# MM_Performer.net
KiCad netlist of a schematic drawn in EAGLE
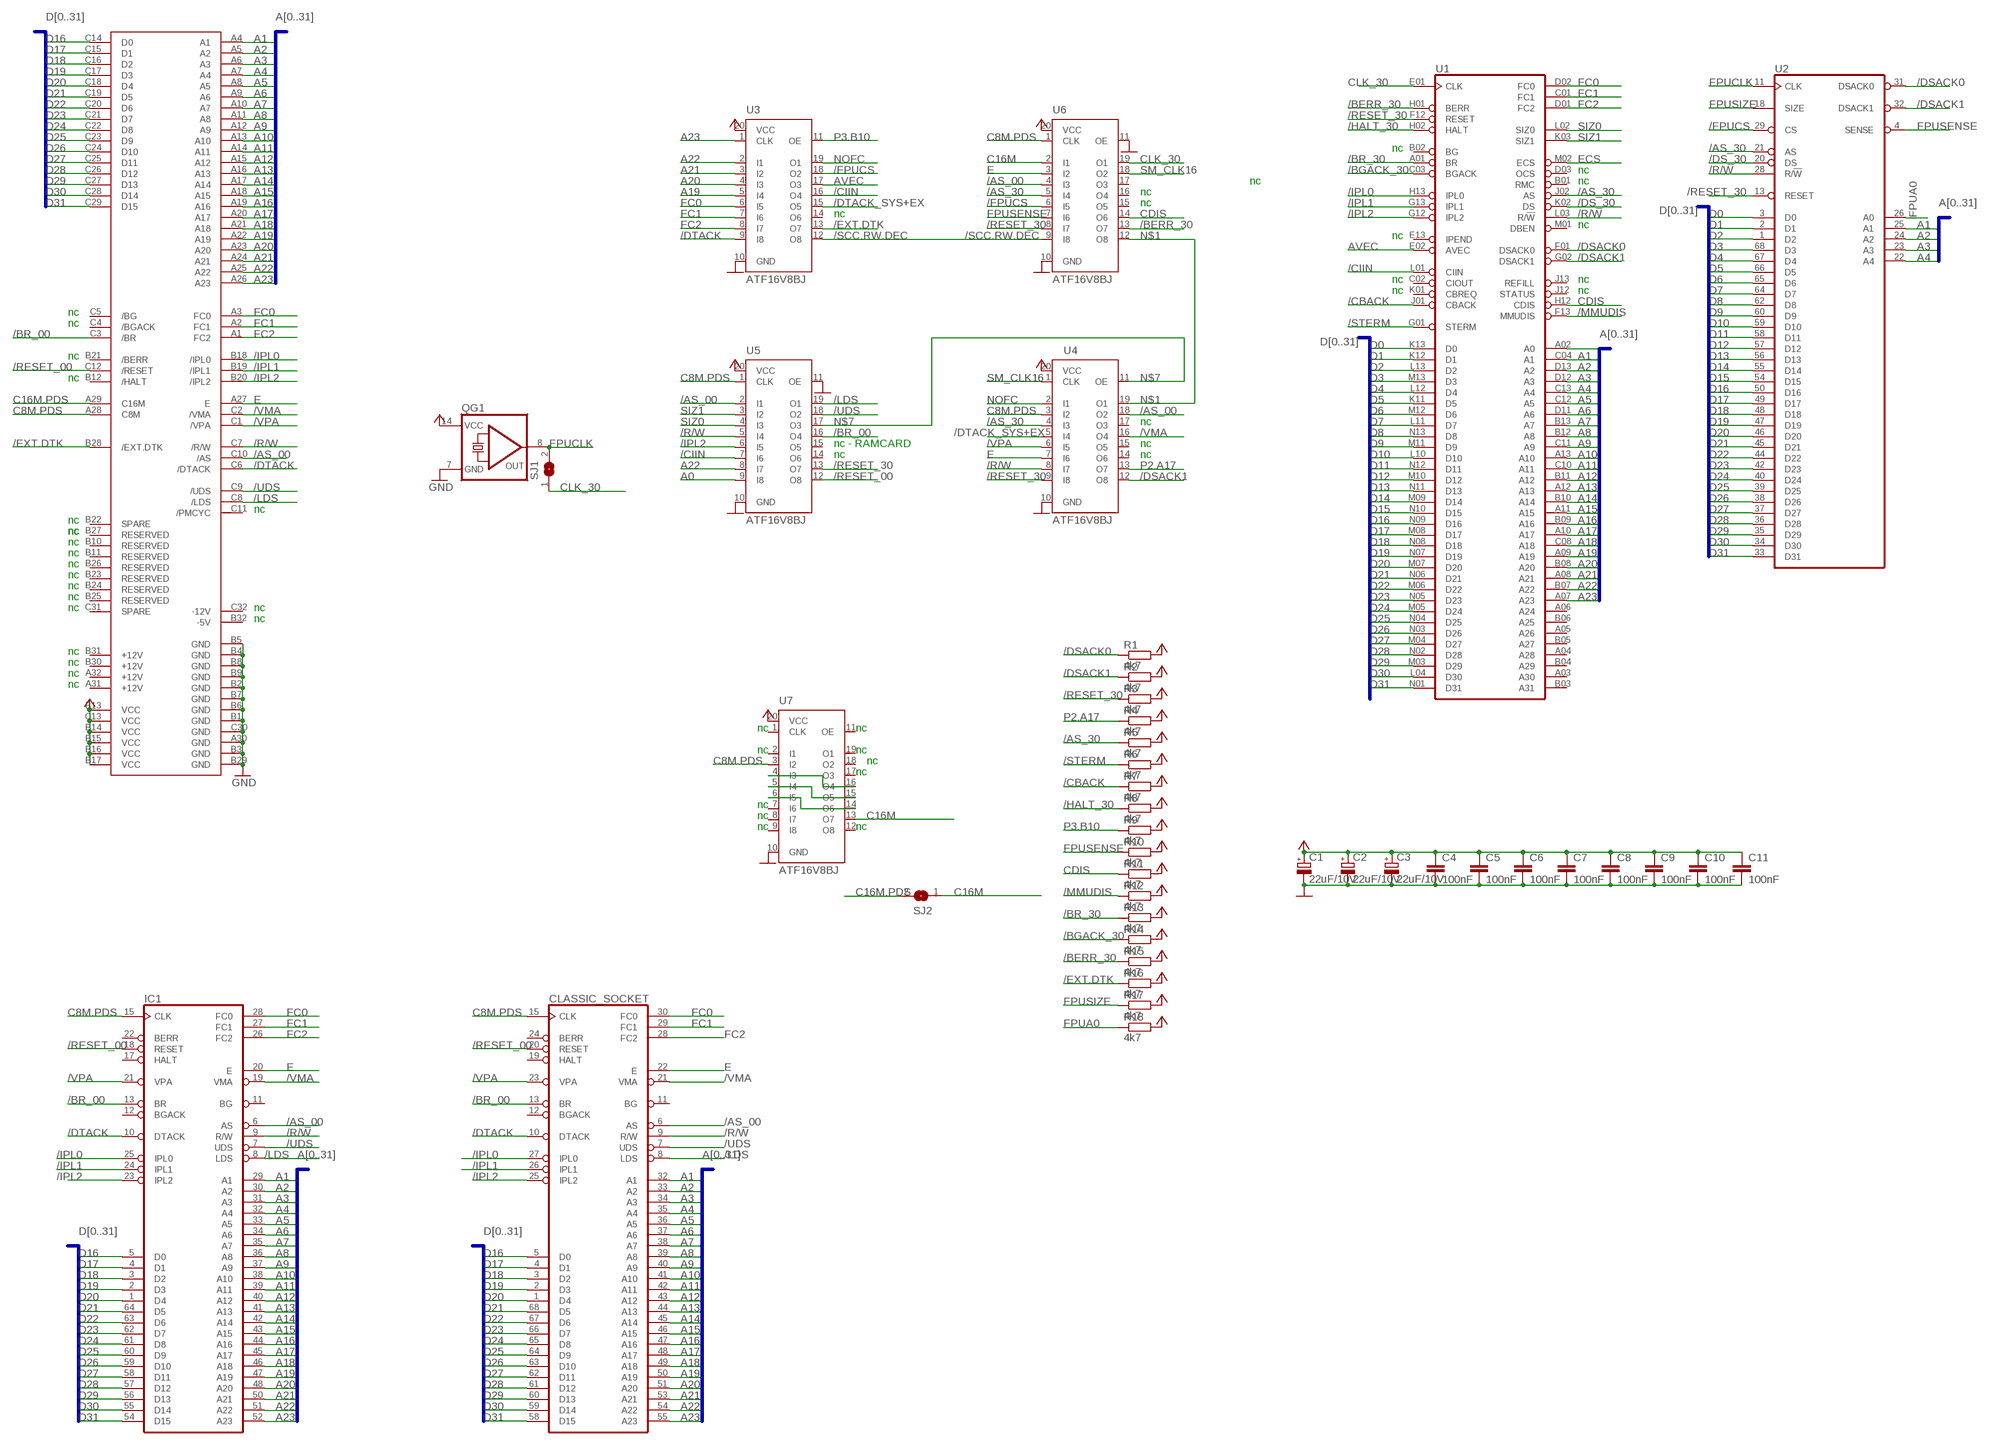
[diagram p0: schematic, sheet 1]

(export (version "E")
  (design (tool "Eeschema 10.0.6"))
  (components
    (comp (ref "C1")
      (value "22uF/10V")
      (footprint "eagle-import:C_6032-28W")
      (libsource (lib "eagle-import") (part "CPOL-EUC/6032-28W"))
    )
    (comp (ref "C2")
      (value "22uF/10V")
      (footprint "eagle-import:C_6032-28W")
      (libsource (lib "eagle-import") (part "CPOL-EUC/6032-28W"))
    )
    (comp (ref "C3")
      (value "22uF/10V")
      (footprint "eagle-import:C_6032-28W")
      (libsource (lib "eagle-import") (part "CPOL-EUC/6032-28W"))
    )
    (comp (ref "C4")
      (value "100nF")
      (footprint "eagle-import:C1206")
      (libsource (lib "eagle-import") (part "C-EUC1206"))
    )
    (comp (ref "C5")
      (value "100nF")
      (footprint "eagle-import:C1206")
      (libsource (lib "eagle-import") (part "C-EUC1206"))
    )
    (comp (ref "C6")
      (value "100nF")
      (footprint "eagle-import:C1206")
      (libsource (lib "eagle-import") (part "C-EUC1206"))
    )
    (comp (ref "C7")
      (value "100nF")
      (footprint "eagle-import:C1206")
      (libsource (lib "eagle-import") (part "C-EUC1206"))
    )
    (comp (ref "C8")
      (value "100nF")
      (footprint "eagle-import:C1206")
      (libsource (lib "eagle-import") (part "C-EUC1206"))
    )
    (comp (ref "C9")
      (value "100nF")
      (footprint "eagle-import:C1206")
      (libsource (lib "eagle-import") (part "C-EUC1206"))
    )
    (comp (ref "C10")
      (value "100nF")
      (footprint "eagle-import:C1206")
      (libsource (lib "eagle-import") (part "C-EUC1206"))
    )
    (comp (ref "C11")
      (value "100nF")
      (footprint "eagle-import:C1206")
      (libsource (lib "eagle-import") (part "C-EUC1206"))
    )
    (comp (ref "CLASSIC_SOCKET")
      (value "MC68000FN-SOC")
      (footprint "eagle-import:PLCC68-S")
      (libsource (lib "eagle-import") (part "MC68000FN-SOC"))
    )
    (comp (ref "IC1")
      (value "MC68000P")
      (footprint "eagle-import:DIL64")
      (libsource (lib "eagle-import") (part "MC68000P"))
    )
    (comp (ref "QG1")
      (value "QG5860")
      (footprint "eagle-import:DIL14S")
      (libsource (lib "eagle-import") (part "QG5860"))
    )
    (comp (ref "R1")
      (value "4k7")
      (footprint "eagle-import:R1206")
      (libsource (lib "eagle-import") (part "R-EU_R1206"))
    )
    (comp (ref "R2")
      (value "4k7")
      (footprint "eagle-import:R1206")
      (libsource (lib "eagle-import") (part "R-EU_R1206"))
    )
    (comp (ref "R3")
      (value "4k7")
      (footprint "eagle-import:R1206")
      (libsource (lib "eagle-import") (part "R-EU_R1206"))
    )
    (comp (ref "R4")
      (value "4k7")
      (footprint "eagle-import:R1206")
      (libsource (lib "eagle-import") (part "R-EU_R1206"))
    )
    (comp (ref "R5")
      (value "4k7")
      (footprint "eagle-import:R1206")
      (libsource (lib "eagle-import") (part "R-EU_R1206"))
    )
    (comp (ref "R6")
      (value "4k7")
      (footprint "eagle-import:R1206")
      (libsource (lib "eagle-import") (part "R-EU_R1206"))
    )
    (comp (ref "R7")
      (value "4k7")
      (footprint "eagle-import:R1206")
      (libsource (lib "eagle-import") (part "R-EU_R1206"))
    )
    (comp (ref "R8")
      (value "4k7")
      (footprint "eagle-import:R1206")
      (libsource (lib "eagle-import") (part "R-EU_R1206"))
    )
    (comp (ref "R9")
      (value "4k7")
      (footprint "eagle-import:R1206")
      (libsource (lib "eagle-import") (part "R-EU_R1206"))
    )
    (comp (ref "R10")
      (value "4k7")
      (footprint "eagle-import:R1206")
      (libsource (lib "eagle-import") (part "R-EU_R1206"))
    )
    (comp (ref "R11")
      (value "4k7")
      (footprint "eagle-import:R1206")
      (libsource (lib "eagle-import") (part "R-EU_R1206"))
    )
    (comp (ref "R12")
      (value "4k7")
      (footprint "eagle-import:R1206")
      (libsource (lib "eagle-import") (part "R-EU_R1206"))
    )
    (comp (ref "R13")
      (value "4k7")
      (footprint "eagle-import:R1206")
      (libsource (lib "eagle-import") (part "R-EU_R1206"))
    )
    (comp (ref "R14")
      (value "4k7")
      (footprint "eagle-import:R1206")
      (libsource (lib "eagle-import") (part "R-EU_R1206"))
    )
    (comp (ref "R15")
      (value "4k7")
      (footprint "eagle-import:R1206")
      (libsource (lib "eagle-import") (part "R-EU_R1206"))
    )
    (comp (ref "R16")
      (value "4k7")
      (footprint "eagle-import:R1206")
      (libsource (lib "eagle-import") (part "R-EU_R1206"))
    )
    (comp (ref "R17")
      (value "4k7")
      (footprint "eagle-import:R1206")
      (libsource (lib "eagle-import") (part "R-EU_R1206"))
    )
    (comp (ref "R18")
      (value "4k7")
      (footprint "eagle-import:R1206")
      (libsource (lib "eagle-import") (part "R-EU_R1206"))
    )
    (comp (ref "SJ1") (value "SJ") (footprint "eagle-import:SJ") (libsource (lib "eagle-import") (part "SJ")))
    (comp (ref "SJ2") (value "SJ") (footprint "eagle-import:SJ") (libsource (lib "eagle-import") (part "SJ")))
    (comp (ref "U$1")
      (value "MAC_SE_PDS")
      (footprint "eagle-import:MABC96_MIRROR")
      (libsource (lib "eagle-import") (part "MAC_SE_PDS"))
    )
    (comp (ref "U1")
      (value "MC68030RC")
      (footprint "eagle-import:MPGA128")
      (fields (field (name "MF") "MOTOROLA") (field (name "MPN") "MC68030RC50C"))
      (libsource (lib "eagle-import") (part "MC68030RC"))
    )
    (comp (ref "U2")
      (value "MC68881FN-SOC")
      (footprint "eagle-import:PLCC68-S")
      (libsource (lib "eagle-import") (part "MC68881FN-SOC"))
    )
    (comp (ref "U3")
      (value "ATF16V8BJ")
      (footprint "eagle-import:PLCC20")
      (fields (field (name "MPN") "ATF16V8CZ-15JU"))
      (libsource (lib "eagle-import") (part "ATF16V8BJ"))
    )
    (comp (ref "U4")
      (value "ATF16V8BJ")
      (footprint "eagle-import:PLCC20")
      (fields (field (name "MPN") "ATF16V8CZ-15JU"))
      (libsource (lib "eagle-import") (part "ATF16V8BJ"))
    )
    (comp (ref "U5")
      (value "ATF16V8BJ")
      (footprint "eagle-import:PLCC20")
      (fields (field (name "MPN") "ATF16V8CZ-15JU"))
      (libsource (lib "eagle-import") (part "ATF16V8BJ"))
    )
    (comp (ref "U6")
      (value "ATF16V8BJ")
      (footprint "eagle-import:PLCC20")
      (fields (field (name "MPN") "ATF16V8CZ-15JU"))
      (libsource (lib "eagle-import") (part "ATF16V8BJ"))
    )
    (comp (ref "U7")
      (value "ATF16V8BJ")
      (footprint "eagle-import:PLCC20")
      (fields (field (name "MPN") "ATF16V8CZ-15JU"))
      (libsource (lib "eagle-import") (part "ATF16V8BJ"))
    )
  )
  (nets
    (net (code "9") (name "/A0") (class "Default")
      (node (ref "U1") (pin "A02") (pinfunction "A0_A02") (pintype "output"))
      (node (ref "U5") (pin "9") (pinfunction "I8_9") (pintype "input"))
    )
    (net (code "10") (name "/A1") (class "Default")
      (node (ref "CLASSIC_SOCKET") (pin "32") (pinfunction "A1_32") (pintype "output"))
      (node (ref "IC1") (pin "29") (pinfunction "A1_29") (pintype "output"))
      (node (ref "U$1") (pin "A4") (pinfunction "A1_A4") (pintype "bidirectional"))
      (node (ref "U1") (pin "C04") (pinfunction "A1_C04") (pintype "output"))
      (node (ref "U2") (pin "25") (pinfunction "A1_25") (pintype "input"))
    )
    (net (code "11") (name "/A2") (class "Default")
      (node (ref "CLASSIC_SOCKET") (pin "33") (pinfunction "A2_33") (pintype "output"))
      (node (ref "IC1") (pin "30") (pinfunction "A2_30") (pintype "output"))
      (node (ref "U$1") (pin "A5") (pinfunction "A2_A5") (pintype "bidirectional"))
      (node (ref "U1") (pin "D13") (pinfunction "A2_D13") (pintype "output"))
      (node (ref "U2") (pin "24") (pinfunction "A2_24") (pintype "input"))
    )
    (net (code "12") (name "/A3") (class "Default")
      (node (ref "CLASSIC_SOCKET") (pin "34") (pinfunction "A3_34") (pintype "output"))
      (node (ref "IC1") (pin "31") (pinfunction "A3_31") (pintype "output"))
      (node (ref "U$1") (pin "A6") (pinfunction "A3_A6") (pintype "bidirectional"))
      (node (ref "U1") (pin "D12") (pinfunction "A3_D12") (pintype "output"))
      (node (ref "U2") (pin "23") (pinfunction "A3_23") (pintype "input"))
    )
    (net (code "13") (name "/A4") (class "Default")
      (node (ref "CLASSIC_SOCKET") (pin "35") (pinfunction "A4_35") (pintype "output"))
      (node (ref "IC1") (pin "32") (pinfunction "A4_32") (pintype "output"))
      (node (ref "U$1") (pin "A7") (pinfunction "A4_A7") (pintype "bidirectional"))
      (node (ref "U1") (pin "C13") (pinfunction "A4_C13") (pintype "output"))
      (node (ref "U2") (pin "22") (pinfunction "A4_22") (pintype "input"))
    )
    (net (code "14") (name "/A5") (class "Default")
      (node (ref "CLASSIC_SOCKET") (pin "36") (pinfunction "A5_36") (pintype "output"))
      (node (ref "IC1") (pin "33") (pinfunction "A5_33") (pintype "output"))
      (node (ref "U$1") (pin "A8") (pinfunction "A5_A8") (pintype "bidirectional"))
      (node (ref "U1") (pin "C12") (pinfunction "A5_C12") (pintype "output"))
    )
    (net (code "15") (name "/A6") (class "Default")
      (node (ref "CLASSIC_SOCKET") (pin "37") (pinfunction "A6_37") (pintype "output"))
      (node (ref "IC1") (pin "34") (pinfunction "A6_34") (pintype "output"))
      (node (ref "U$1") (pin "A9") (pinfunction "A6_A9") (pintype "bidirectional"))
      (node (ref "U1") (pin "D11") (pinfunction "A6_D11") (pintype "output"))
    )
    (net (code "16") (name "/A7") (class "Default")
      (node (ref "CLASSIC_SOCKET") (pin "38") (pinfunction "A7_38") (pintype "output"))
      (node (ref "IC1") (pin "35") (pinfunction "A7_35") (pintype "output"))
      (node (ref "U$1") (pin "A10") (pinfunction "A7_A10") (pintype "bidirectional"))
      (node (ref "U1") (pin "B13") (pinfunction "A7_B13") (pintype "output"))
    )
    (net (code "17") (name "/A8") (class "Default")
      (node (ref "CLASSIC_SOCKET") (pin "39") (pinfunction "A8_39") (pintype "output"))
      (node (ref "IC1") (pin "36") (pinfunction "A8_36") (pintype "output"))
      (node (ref "U$1") (pin "A11") (pinfunction "A8_A11") (pintype "bidirectional"))
      (node (ref "U1") (pin "B12") (pinfunction "A8_B12") (pintype "output"))
    )
    (net (code "18") (name "/A9") (class "Default")
      (node (ref "CLASSIC_SOCKET") (pin "40") (pinfunction "A9_40") (pintype "output"))
      (node (ref "IC1") (pin "37") (pinfunction "A9_37") (pintype "output"))
      (node (ref "U$1") (pin "A12") (pinfunction "A9_A12") (pintype "bidirectional"))
      (node (ref "U1") (pin "C11") (pinfunction "A9_C11") (pintype "output"))
    )
    (net (code "19") (name "/A10") (class "Default")
      (node (ref "CLASSIC_SOCKET") (pin "41") (pinfunction "A10_41") (pintype "output"))
      (node (ref "IC1") (pin "38") (pinfunction "A10_38") (pintype "output"))
      (node (ref "U$1") (pin "A13") (pinfunction "A10_A13") (pintype "bidirectional"))
      (node (ref "U1") (pin "A13") (pinfunction "A10_A13") (pintype "output"))
    )
    (net (code "20") (name "/A11") (class "Default")
      (node (ref "CLASSIC_SOCKET") (pin "42") (pinfunction "A11_42") (pintype "output"))
      (node (ref "IC1") (pin "39") (pinfunction "A11_39") (pintype "output"))
      (node (ref "U$1") (pin "A14") (pinfunction "A11_A14") (pintype "bidirectional"))
      (node (ref "U1") (pin "C10") (pinfunction "A11_C10") (pintype "output"))
    )
    (net (code "21") (name "/A12") (class "Default")
      (node (ref "CLASSIC_SOCKET") (pin "43") (pinfunction "A12_43") (pintype "output"))
      (node (ref "IC1") (pin "40") (pinfunction "A12_40") (pintype "output"))
      (node (ref "U$1") (pin "A15") (pinfunction "A12_A15") (pintype "bidirectional"))
      (node (ref "U1") (pin "B11") (pinfunction "A12_B11") (pintype "output"))
    )
    (net (code "22") (name "/A13") (class "Default")
      (node (ref "CLASSIC_SOCKET") (pin "44") (pinfunction "A13_44") (pintype "output"))
      (node (ref "IC1") (pin "41") (pinfunction "A13_41") (pintype "output"))
      (node (ref "U$1") (pin "A16") (pinfunction "A13_A16") (pintype "bidirectional"))
      (node (ref "U1") (pin "A12") (pinfunction "A13_A12") (pintype "output"))
    )
    (net (code "23") (name "/A14") (class "Default")
      (node (ref "CLASSIC_SOCKET") (pin "45") (pinfunction "A14_45") (pintype "output"))
      (node (ref "IC1") (pin "42") (pinfunction "A14_42") (pintype "output"))
      (node (ref "U$1") (pin "A17") (pinfunction "A14_A17") (pintype "bidirectional"))
      (node (ref "U1") (pin "B10") (pinfunction "A14_B10") (pintype "output"))
    )
    (net (code "24") (name "/A15") (class "Default")
      (node (ref "CLASSIC_SOCKET") (pin "46") (pinfunction "A15_46") (pintype "output"))
      (node (ref "IC1") (pin "43") (pinfunction "A15_43") (pintype "output"))
      (node (ref "U$1") (pin "A18") (pinfunction "A15_A18") (pintype "bidirectional"))
      (node (ref "U1") (pin "A11") (pinfunction "A15_A11") (pintype "output"))
    )
    (net (code "25") (name "/A16") (class "Default")
      (node (ref "CLASSIC_SOCKET") (pin "47") (pinfunction "A16_47") (pintype "output"))
      (node (ref "IC1") (pin "44") (pinfunction "A16_44") (pintype "output"))
      (node (ref "U$1") (pin "A19") (pinfunction "A16_A19") (pintype "bidirectional"))
      (node (ref "U1") (pin "B09") (pinfunction "A16_B09") (pintype "output"))
    )
    (net (code "26") (name "/A17") (class "Default")
      (node (ref "CLASSIC_SOCKET") (pin "48") (pinfunction "A17_48") (pintype "output"))
      (node (ref "IC1") (pin "45") (pinfunction "A17_45") (pintype "output"))
      (node (ref "U$1") (pin "A20") (pinfunction "A17_A20") (pintype "bidirectional"))
      (node (ref "U1") (pin "A10") (pinfunction "A17_A10") (pintype "output"))
    )
    (net (code "27") (name "/A18") (class "Default")
      (node (ref "CLASSIC_SOCKET") (pin "49") (pinfunction "A18_49") (pintype "output"))
      (node (ref "IC1") (pin "46") (pinfunction "A18_46") (pintype "output"))
      (node (ref "U$1") (pin "A21") (pinfunction "A18_A21") (pintype "bidirectional"))
      (node (ref "U1") (pin "C08") (pinfunction "A18_C08") (pintype "output"))
    )
    (net (code "28") (name "/A19") (class "Default")
      (node (ref "CLASSIC_SOCKET") (pin "50") (pinfunction "A19_50") (pintype "output"))
      (node (ref "IC1") (pin "47") (pinfunction "A19_47") (pintype "output"))
      (node (ref "U$1") (pin "A22") (pinfunction "A19_A22") (pintype "bidirectional"))
      (node (ref "U1") (pin "A09") (pinfunction "A19_A09") (pintype "output"))
      (node (ref "U3") (pin "5") (pinfunction "I4_5") (pintype "input"))
    )
    (net (code "29") (name "/A20") (class "Default")
      (node (ref "CLASSIC_SOCKET") (pin "51") (pinfunction "A20_51") (pintype "output"))
      (node (ref "IC1") (pin "48") (pinfunction "A20_48") (pintype "output"))
      (node (ref "U$1") (pin "A23") (pinfunction "A20_A23") (pintype "bidirectional"))
      (node (ref "U1") (pin "B08") (pinfunction "A20_B08") (pintype "output"))
      (node (ref "U3") (pin "4") (pinfunction "I3_4") (pintype "input"))
    )
    (net (code "30") (name "/A21") (class "Default")
      (node (ref "CLASSIC_SOCKET") (pin "53") (pinfunction "A21_53") (pintype "output"))
      (node (ref "IC1") (pin "50") (pinfunction "A21_50") (pintype "output"))
      (node (ref "U$1") (pin "A24") (pinfunction "A21_A24") (pintype "bidirectional"))
      (node (ref "U1") (pin "A08") (pinfunction "A21_A08") (pintype "output"))
      (node (ref "U3") (pin "3") (pinfunction "I2_3") (pintype "input"))
    )
    (net (code "31") (name "/A22") (class "Default")
      (node (ref "CLASSIC_SOCKET") (pin "54") (pinfunction "A22_54") (pintype "output"))
      (node (ref "IC1") (pin "51") (pinfunction "A22_51") (pintype "output"))
      (node (ref "U$1") (pin "A25") (pinfunction "A22_A25") (pintype "bidirectional"))
      (node (ref "U1") (pin "B07") (pinfunction "A22_B07") (pintype "output"))
      (node (ref "U3") (pin "2") (pinfunction "I1_2") (pintype "input"))
      (node (ref "U5") (pin "8") (pinfunction "I7_8") (pintype "input"))
    )
    (net (code "32") (name "/A23") (class "Default")
      (node (ref "CLASSIC_SOCKET") (pin "55") (pinfunction "A23_55") (pintype "output"))
      (node (ref "IC1") (pin "52") (pinfunction "A23_52") (pintype "output"))
      (node (ref "U$1") (pin "A26") (pinfunction "A23_A26") (pintype "bidirectional"))
      (node (ref "U1") (pin "A07") (pinfunction "A23_A07") (pintype "output"))
      (node (ref "U3") (pin "1") (pinfunction "CLK_1") (pintype "input"))
    )
    (net (code "33") (name "/AVEC") (class "Default")
      (node (ref "U1") (pin "E02") (pinfunction "AVEC_E02") (pintype "input"))
      (node (ref "U3") (pin "17") (pinfunction "O3_17") (pintype "output"))
    )
    (net (code "35") (name "/C8M.PDS") (class "Default")
      (node (ref "CLASSIC_SOCKET") (pin "15") (pinfunction "CLK_15") (pintype "input"))
      (node (ref "IC1") (pin "15") (pinfunction "CLK_15") (pintype "input"))
      (node (ref "U$1") (pin "A28") (pinfunction "C8M_A28") (pintype "bidirectional"))
      (node (ref "U4") (pin "3") (pinfunction "I2_3") (pintype "input"))
      (node (ref "U5") (pin "1") (pinfunction "CLK_1") (pintype "input"))
      (node (ref "U6") (pin "1") (pinfunction "CLK_1") (pintype "input"))
      (node (ref "U7") (pin "3") (pinfunction "I2_3") (pintype "input"))
    )
    (net (code "36") (name "/C16M") (class "Default")
      (node (ref "SJ2") (pin "1") (pinfunction "1_1") (pintype "passive"))
      (node (ref "U6") (pin "2") (pinfunction "I1_2") (pintype "input"))
      (node (ref "U7") (pin "13") (pinfunction "O7_13") (pintype "output"))
    )
    (net (code "37") (name "/C16M.PDS") (class "Default")
      (node (ref "SJ2") (pin "2") (pinfunction "2_2") (pintype "passive"))
      (node (ref "U$1") (pin "A29") (pinfunction "C16M_A29") (pintype "bidirectional"))
    )
    (net (code "38") (name "/CDIS") (class "Default")
      (node (ref "R11") (pin "1") (pinfunction "1_1") (pintype "passive"))
      (node (ref "U1") (pin "H12") (pinfunction "CDIS_H12") (pintype "input"))
      (node (ref "U6") (pin "14") (pinfunction "O6_14") (pintype "output"))
    )
    (net (code "39") (name "/CLK_30") (class "Default")
      (node (ref "SJ1") (pin "1") (pinfunction "1_1") (pintype "passive"))
      (node (ref "U1") (pin "E01") (pinfunction "CLK_E01") (pintype "input"))
      (node (ref "U6") (pin "19") (pinfunction "O1_19") (pintype "output"))
    )
    (net (code "40") (name "/D0") (class "Default")
      (node (ref "U1") (pin "K13") (pinfunction "D0_K13") (pintype "bidirectional"))
      (node (ref "U2") (pin "3") (pinfunction "D0_3") (pintype "bidirectional"))
    )
    (net (code "41") (name "/D1") (class "Default")
      (node (ref "U1") (pin "K12") (pinfunction "D1_K12") (pintype "bidirectional"))
      (node (ref "U2") (pin "2") (pinfunction "D1_2") (pintype "bidirectional"))
    )
    (net (code "42") (name "/D2") (class "Default")
      (node (ref "U1") (pin "L13") (pinfunction "D2_L13") (pintype "bidirectional"))
      (node (ref "U2") (pin "1") (pinfunction "D2_1") (pintype "bidirectional"))
    )
    (net (code "43") (name "/D3") (class "Default")
      (node (ref "U1") (pin "M13") (pinfunction "D3_M13") (pintype "bidirectional"))
      (node (ref "U2") (pin "68") (pinfunction "D3_68") (pintype "bidirectional"))
    )
    (net (code "44") (name "/D4") (class "Default")
      (node (ref "U1") (pin "L12") (pinfunction "D4_L12") (pintype "bidirectional"))
      (node (ref "U2") (pin "67") (pinfunction "D4_67") (pintype "bidirectional"))
    )
    (net (code "45") (name "/D5") (class "Default")
      (node (ref "U1") (pin "K11") (pinfunction "D5_K11") (pintype "bidirectional"))
      (node (ref "U2") (pin "66") (pinfunction "D5_66") (pintype "bidirectional"))
    )
    (net (code "46") (name "/D6") (class "Default")
      (node (ref "U1") (pin "M12") (pinfunction "D6_M12") (pintype "bidirectional"))
      (node (ref "U2") (pin "65") (pinfunction "D6_65") (pintype "bidirectional"))
    )
    (net (code "47") (name "/D7") (class "Default")
      (node (ref "U1") (pin "L11") (pinfunction "D7_L11") (pintype "bidirectional"))
      (node (ref "U2") (pin "64") (pinfunction "D7_64") (pintype "bidirectional"))
    )
    (net (code "48") (name "/D8") (class "Default")
      (node (ref "U1") (pin "N13") (pinfunction "D8_N13") (pintype "bidirectional"))
      (node (ref "U2") (pin "62") (pinfunction "D8_62") (pintype "bidirectional"))
    )
    (net (code "49") (name "/D9") (class "Default")
      (node (ref "U1") (pin "M11") (pinfunction "D9_M11") (pintype "bidirectional"))
      (node (ref "U2") (pin "60") (pinfunction "D9_60") (pintype "bidirectional"))
    )
    (net (code "50") (name "/D10") (class "Default")
      (node (ref "U1") (pin "L10") (pinfunction "D10_L10") (pintype "bidirectional"))
      (node (ref "U2") (pin "59") (pinfunction "D10_59") (pintype "bidirectional"))
    )
    (net (code "51") (name "/D11") (class "Default")
      (node (ref "U1") (pin "N12") (pinfunction "D11_N12") (pintype "bidirectional"))
      (node (ref "U2") (pin "58") (pinfunction "D11_58") (pintype "bidirectional"))
    )
    (net (code "52") (name "/D12") (class "Default")
      (node (ref "U1") (pin "M10") (pinfunction "D12_M10") (pintype "bidirectional"))
      (node (ref "U2") (pin "57") (pinfunction "D12_57") (pintype "bidirectional"))
    )
    (net (code "53") (name "/D13") (class "Default")
      (node (ref "U1") (pin "N11") (pinfunction "D13_N11") (pintype "bidirectional"))
      (node (ref "U2") (pin "56") (pinfunction "D13_56") (pintype "bidirectional"))
    )
    (net (code "54") (name "/D14") (class "Default")
      (node (ref "U1") (pin "M09") (pinfunction "D14_M09") (pintype "bidirectional"))
      (node (ref "U2") (pin "55") (pinfunction "D14_55") (pintype "bidirectional"))
    )
    (net (code "55") (name "/D15") (class "Default")
      (node (ref "U1") (pin "N10") (pinfunction "D15_N10") (pintype "bidirectional"))
      (node (ref "U2") (pin "54") (pinfunction "D15_54") (pintype "bidirectional"))
    )
    (net (code "56") (name "/D16") (class "Default")
      (node (ref "CLASSIC_SOCKET") (pin "5") (pinfunction "D0_5") (pintype "bidirectional"))
      (node (ref "IC1") (pin "5") (pinfunction "D0_5") (pintype "bidirectional"))
      (node (ref "U$1") (pin "C14") (pinfunction "D0_C14") (pintype "bidirectional"))
      (node (ref "U1") (pin "N09") (pinfunction "D16_N09") (pintype "bidirectional"))
      (node (ref "U2") (pin "50") (pinfunction "D16_50") (pintype "bidirectional"))
    )
    (net (code "57") (name "/D17") (class "Default")
      (node (ref "CLASSIC_SOCKET") (pin "4") (pinfunction "D1_4") (pintype "bidirectional"))
      (node (ref "IC1") (pin "4") (pinfunction "D1_4") (pintype "bidirectional"))
      (node (ref "U$1") (pin "C15") (pinfunction "D1_C15") (pintype "bidirectional"))
      (node (ref "U1") (pin "M08") (pinfunction "D17_M08") (pintype "bidirectional"))
      (node (ref "U2") (pin "49") (pinfunction "D17_49") (pintype "bidirectional"))
    )
    (net (code "58") (name "/D18") (class "Default")
      (node (ref "CLASSIC_SOCKET") (pin "3") (pinfunction "D2_3") (pintype "bidirectional"))
      (node (ref "IC1") (pin "3") (pinfunction "D2_3") (pintype "bidirectional"))
      (node (ref "U$1") (pin "C16") (pinfunction "D2_C16") (pintype "bidirectional"))
      (node (ref "U1") (pin "N08") (pinfunction "D18_N08") (pintype "bidirectional"))
      (node (ref "U2") (pin "48") (pinfunction "D18_48") (pintype "bidirectional"))
    )
    (net (code "59") (name "/D19") (class "Default")
      (node (ref "CLASSIC_SOCKET") (pin "2") (pinfunction "D3_2") (pintype "bidirectional"))
      (node (ref "IC1") (pin "2") (pinfunction "D3_2") (pintype "bidirectional"))
      (node (ref "U$1") (pin "C17") (pinfunction "D3_C17") (pintype "bidirectional"))
      (node (ref "U1") (pin "N07") (pinfunction "D19_N07") (pintype "bidirectional"))
      (node (ref "U2") (pin "47") (pinfunction "D19_47") (pintype "bidirectional"))
    )
    (net (code "60") (name "/D20") (class "Default")
      (node (ref "CLASSIC_SOCKET") (pin "1") (pinfunction "D4_1") (pintype "bidirectional"))
      (node (ref "IC1") (pin "1") (pinfunction "D4_1") (pintype "bidirectional"))
      (node (ref "U$1") (pin "C18") (pinfunction "D4_C18") (pintype "bidirectional"))
      (node (ref "U1") (pin "M07") (pinfunction "D20_M07") (pintype "bidirectional"))
      (node (ref "U2") (pin "46") (pinfunction "D20_46") (pintype "bidirectional"))
    )
    (net (code "61") (name "/D21") (class "Default")
      (node (ref "CLASSIC_SOCKET") (pin "68") (pinfunction "D5_68") (pintype "bidirectional"))
      (node (ref "IC1") (pin "64") (pinfunction "D5_64") (pintype "bidirectional"))
      (node (ref "U$1") (pin "C19") (pinfunction "D5_C19") (pintype "bidirectional"))
      (node (ref "U1") (pin "N06") (pinfunction "D21_N06") (pintype "bidirectional"))
      (node (ref "U2") (pin "45") (pinfunction "D21_45") (pintype "bidirectional"))
    )
    (net (code "62") (name "/D22") (class "Default")
      (node (ref "CLASSIC_SOCKET") (pin "67") (pinfunction "D6_67") (pintype "bidirectional"))
      (node (ref "IC1") (pin "63") (pinfunction "D6_63") (pintype "bidirectional"))
      (node (ref "U$1") (pin "C20") (pinfunction "D6_C20") (pintype "bidirectional"))
      (node (ref "U1") (pin "M06") (pinfunction "D22_M06") (pintype "bidirectional"))
      (node (ref "U2") (pin "44") (pinfunction "D22_44") (pintype "bidirectional"))
    )
    (net (code "63") (name "/D23") (class "Default")
      (node (ref "CLASSIC_SOCKET") (pin "66") (pinfunction "D7_66") (pintype "bidirectional"))
      (node (ref "IC1") (pin "62") (pinfunction "D7_62") (pintype "bidirectional"))
      (node (ref "U$1") (pin "C21") (pinfunction "D7_C21") (pintype "bidirectional"))
      (node (ref "U1") (pin "N05") (pinfunction "D23_N05") (pintype "bidirectional"))
      (node (ref "U2") (pin "42") (pinfunction "D23_42") (pintype "bidirectional"))
    )
    (net (code "64") (name "/D24") (class "Default")
      (node (ref "CLASSIC_SOCKET") (pin "65") (pinfunction "D8_65") (pintype "bidirectional"))
      (node (ref "IC1") (pin "61") (pinfunction "D8_61") (pintype "bidirectional"))
      (node (ref "U$1") (pin "C22") (pinfunction "D8_C22") (pintype "bidirectional"))
      (node (ref "U1") (pin "M05") (pinfunction "D24_M05") (pintype "bidirectional"))
      (node (ref "U2") (pin "40") (pinfunction "D24_40") (pintype "bidirectional"))
    )
    (net (code "65") (name "/D25") (class "Default")
      (node (ref "CLASSIC_SOCKET") (pin "64") (pinfunction "D9_64") (pintype "bidirectional"))
      (node (ref "IC1") (pin "60") (pinfunction "D9_60") (pintype "bidirectional"))
      (node (ref "U$1") (pin "C23") (pinfunction "D9_C23") (pintype "bidirectional"))
      (node (ref "U1") (pin "N04") (pinfunction "D25_N04") (pintype "bidirectional"))
      (node (ref "U2") (pin "39") (pinfunction "D25_39") (pintype "bidirectional"))
    )
    (net (code "66") (name "/D26") (class "Default")
      (node (ref "CLASSIC_SOCKET") (pin "63") (pinfunction "D10_63") (pintype "bidirectional"))
      (node (ref "IC1") (pin "59") (pinfunction "D10_59") (pintype "bidirectional"))
      (node (ref "U$1") (pin "C24") (pinfunction "D10_C24") (pintype "bidirectional"))
      (node (ref "U1") (pin "N03") (pinfunction "D26_N03") (pintype "bidirectional"))
      (node (ref "U2") (pin "38") (pinfunction "D26_38") (pintype "bidirectional"))
    )
    (net (code "67") (name "/D27") (class "Default")
      (node (ref "CLASSIC_SOCKET") (pin "62") (pinfunction "D11_62") (pintype "bidirectional"))
      (node (ref "IC1") (pin "58") (pinfunction "D11_58") (pintype "bidirectional"))
      (node (ref "U$1") (pin "C25") (pinfunction "D11_C25") (pintype "bidirectional"))
      (node (ref "U1") (pin "M04") (pinfunction "D27_M04") (pintype "bidirectional"))
      (node (ref "U2") (pin "37") (pinfunction "D27_37") (pintype "bidirectional"))
    )
    (net (code "68") (name "/D28") (class "Default")
      (node (ref "CLASSIC_SOCKET") (pin "61") (pinfunction "D12_61") (pintype "bidirectional"))
      (node (ref "IC1") (pin "57") (pinfunction "D12_57") (pintype "bidirectional"))
      (node (ref "U$1") (pin "C26") (pinfunction "D12_C26") (pintype "bidirectional"))
      (node (ref "U1") (pin "N02") (pinfunction "D28_N02") (pintype "bidirectional"))
      (node (ref "U2") (pin "36") (pinfunction "D28_36") (pintype "bidirectional"))
    )
    (net (code "69") (name "/D29") (class "Default")
      (node (ref "CLASSIC_SOCKET") (pin "60") (pinfunction "D13_60") (pintype "bidirectional"))
      (node (ref "IC1") (pin "56") (pinfunction "D13_56") (pintype "bidirectional"))
      (node (ref "U$1") (pin "C27") (pinfunction "D13_C27") (pintype "bidirectional"))
      (node (ref "U1") (pin "M03") (pinfunction "D29_M03") (pintype "bidirectional"))
      (node (ref "U2") (pin "35") (pinfunction "D29_35") (pintype "bidirectional"))
    )
    (net (code "70") (name "/D30") (class "Default")
      (node (ref "CLASSIC_SOCKET") (pin "59") (pinfunction "D14_59") (pintype "bidirectional"))
      (node (ref "IC1") (pin "55") (pinfunction "D14_55") (pintype "bidirectional"))
      (node (ref "U$1") (pin "C28") (pinfunction "D14_C28") (pintype "bidirectional"))
      (node (ref "U1") (pin "L04") (pinfunction "D30_L04") (pintype "bidirectional"))
      (node (ref "U2") (pin "34") (pinfunction "D30_34") (pintype "bidirectional"))
    )
    (net (code "71") (name "/D31") (class "Default")
      (node (ref "CLASSIC_SOCKET") (pin "58") (pinfunction "D15_58") (pintype "bidirectional"))
      (node (ref "IC1") (pin "54") (pinfunction "D15_54") (pintype "bidirectional"))
      (node (ref "U$1") (pin "C29") (pinfunction "D15_C29") (pintype "bidirectional"))
      (node (ref "U1") (pin "N01") (pinfunction "D31_N01") (pintype "bidirectional"))
      (node (ref "U2") (pin "33") (pinfunction "D31_33") (pintype "bidirectional"))
    )
    (net (code "73") (name "/E") (class "Default")
      (node (ref "CLASSIC_SOCKET") (pin "22") (pinfunction "E_22") (pintype "output"))
      (node (ref "IC1") (pin "20") (pinfunction "E_20") (pintype "output"))
      (node (ref "U$1") (pin "A27") (pinfunction "E_A27") (pintype "bidirectional"))
      (node (ref "U4") (pin "7") (pinfunction "I6_7") (pintype "input"))
      (node (ref "U6") (pin "3") (pinfunction "I2_3") (pintype "input"))
    )
    (net (code "74") (name "/ECS") (class "Default")
      (node (ref "U1") (pin "M02") (pinfunction "ECS_M02") (pintype "output"))
    )
    (net (code "75") (name "/FC0") (class "Default")
      (node (ref "CLASSIC_SOCKET") (pin "30") (pinfunction "FC0_30") (pintype "output"))
      (node (ref "IC1") (pin "28") (pinfunction "FC0_28") (pintype "output"))
      (node (ref "U$1") (pin "A3") (pinfunction "FC0_A3") (pintype "bidirectional"))
      (node (ref "U1") (pin "D02") (pinfunction "FC0_D02") (pintype "output"))
      (node (ref "U3") (pin "6") (pinfunction "I5_6") (pintype "input"))
    )
    (net (code "76") (name "/FC1") (class "Default")
      (node (ref "CLASSIC_SOCKET") (pin "29") (pinfunction "FC1_29") (pintype "output"))
      (node (ref "IC1") (pin "27") (pinfunction "FC1_27") (pintype "output"))
      (node (ref "U$1") (pin "A2") (pinfunction "FC1_A2") (pintype "bidirectional"))
      (node (ref "U1") (pin "C01") (pinfunction "FC1_C01") (pintype "output"))
      (node (ref "U3") (pin "7") (pinfunction "I6_7") (pintype "input"))
    )
    (net (code "77") (name "/FC2") (class "Default")
      (node (ref "CLASSIC_SOCKET") (pin "28") (pinfunction "FC2_28") (pintype "output"))
      (node (ref "IC1") (pin "26") (pinfunction "FC2_26") (pintype "output"))
      (node (ref "U$1") (pin "A1") (pinfunction "FC2_A1") (pintype "bidirectional"))
      (node (ref "U1") (pin "D01") (pinfunction "FC2_D01") (pintype "output"))
      (node (ref "U3") (pin "8") (pinfunction "I7_8") (pintype "input"))
    )
    (net (code "78") (name "/FPUA0") (class "Default")
      (node (ref "R18") (pin "1") (pinfunction "1_1") (pintype "passive"))
      (node (ref "U2") (pin "26") (pinfunction "A0_26") (pintype "input"))
    )
    (net (code "79") (name "/FPUCLK") (class "Default")
      (node (ref "QG1") (pin "8") (pinfunction "OUT_8") (pintype "output"))
      (node (ref "SJ1") (pin "2") (pinfunction "2_2") (pintype "passive"))
      (node (ref "U2") (pin "11") (pinfunction "CLK_11") (pintype "input"))
    )
    (net (code "80") (name "/FPUSENSE") (class "Default")
      (node (ref "R10") (pin "1") (pinfunction "1_1") (pintype "passive"))
      (node (ref "U2") (pin "4") (pinfunction "SENSE_4") (pintype "bidirectional"))
      (node (ref "U6") (pin "7") (pinfunction "I6_7") (pintype "input"))
    )
    (net (code "81") (name "/FPUSIZE") (class "Default")
      (node (ref "R17") (pin "1") (pinfunction "1_1") (pintype "passive"))
      (node (ref "U2") (pin "18") (pinfunction "SIZE_18") (pintype "input"))
    )
    (net (code "82") (name "/N$1") (class "Default")
      (node (ref "U4") (pin "19") (pinfunction "O1_19") (pintype "output"))
      (node (ref "U6") (pin "12") (pinfunction "O8_12") (pintype "output"))
    )
    (net (code "83") (name "/N$7") (class "Default")
      (node (ref "U4") (pin "11") (pinfunction "OE_11") (pintype "input"))
      (node (ref "U5") (pin "17") (pinfunction "O3_17") (pintype "output"))
    )
    (net (code "84") (name "/NOFC") (class "Default")
      (node (ref "U3") (pin "19") (pinfunction "O1_19") (pintype "output"))
      (node (ref "U4") (pin "2") (pinfunction "I1_2") (pintype "input"))
    )
    (net (code "85") (name "/P2.A17") (class "Default")
      (node (ref "R4") (pin "1") (pinfunction "1_1") (pintype "passive"))
      (node (ref "U4") (pin "13") (pinfunction "O7_13") (pintype "output"))
    )
    (net (code "86") (name "/P3.B10") (class "Default")
      (node (ref "R9") (pin "1") (pinfunction "1_1") (pintype "passive"))
      (node (ref "U3") (pin "11") (pinfunction "OE_11") (pintype "input"))
    )
    (net (code "87") (name "/SIZ0") (class "Default")
      (node (ref "U1") (pin "L02") (pinfunction "SIZ0_L02") (pintype "output"))
      (node (ref "U5") (pin "4") (pinfunction "I3_4") (pintype "input"))
    )
    (net (code "88") (name "/SIZ1") (class "Default")
      (node (ref "U1") (pin "K03") (pinfunction "SIZ1_K03") (pintype "output"))
      (node (ref "U5") (pin "3") (pinfunction "I2_3") (pintype "input"))
    )
    (net (code "89") (name "/SM_CLK16") (class "Default")
      (node (ref "U4") (pin "1") (pinfunction "CLK_1") (pintype "input"))
      (node (ref "U6") (pin "18") (pinfunction "O2_18") (pintype "output"))
    )
    (net (code "90") (name "/{slash}AS_00") (class "Default")
      (node (ref "CLASSIC_SOCKET") (pin "6") (pinfunction "AS_6") (pintype "output"))
      (node (ref "IC1") (pin "6") (pinfunction "AS_6") (pintype "output"))
      (node (ref "U$1") (pin "C10") (pinfunction "/AS_C10") (pintype "bidirectional"))
      (node (ref "U4") (pin "18") (pinfunction "O2_18") (pintype "output"))
      (node (ref "U5") (pin "2") (pinfunction "I1_2") (pintype "input"))
      (node (ref "U6") (pin "4") (pinfunction "I3_4") (pintype "input"))
    )
    (net (code "91") (name "/{slash}AS_30") (class "Default")
      (node (ref "R5") (pin "1") (pinfunction "1_1") (pintype "passive"))
      (node (ref "U1") (pin "J02") (pinfunction "AS_J02") (pintype "output"))
      (node (ref "U2") (pin "21") (pinfunction "AS_21") (pintype "input"))
      (node (ref "U4") (pin "4") (pinfunction "I3_4") (pintype "input"))
      (node (ref "U6") (pin "5") (pinfunction "I4_5") (pintype "input"))
    )
    (net (code "92") (name "/{slash}BERR_30") (class "Default")
      (node (ref "R15") (pin "1") (pinfunction "1_1") (pintype "passive"))
      (node (ref "U1") (pin "H01") (pinfunction "BERR_H01") (pintype "input"))
      (node (ref "U6") (pin "13") (pinfunction "O7_13") (pintype "output"))
    )
    (net (code "93") (name "/{slash}BGACK_30") (class "Default")
      (node (ref "R14") (pin "1") (pinfunction "1_1") (pintype "passive"))
      (node (ref "U1") (pin "C03") (pinfunction "BGACK_C03") (pintype "input"))
    )
    (net (code "94") (name "/{slash}BR_00") (class "Default")
      (node (ref "CLASSIC_SOCKET") (pin "13") (pinfunction "BR_13") (pintype "input"))
      (node (ref "IC1") (pin "13") (pinfunction "BR_13") (pintype "input"))
      (node (ref "U$1") (pin "C3") (pinfunction "/BR_C3") (pintype "bidirectional"))
      (node (ref "U5") (pin "16") (pinfunction "O4_16") (pintype "output"))
    )
    (net (code "95") (name "/{slash}BR_30") (class "Default")
      (node (ref "R13") (pin "1") (pinfunction "1_1") (pintype "passive"))
      (node (ref "U1") (pin "A01") (pinfunction "BR_A01") (pintype "input"))
    )
    (net (code "96") (name "/{slash}CBACK") (class "Default")
      (node (ref "R7") (pin "1") (pinfunction "1_1") (pintype "passive"))
      (node (ref "U1") (pin "J01") (pinfunction "CBACK_J01") (pintype "input"))
    )
    (net (code "97") (name "/{slash}CIIN") (class "Default")
      (node (ref "U1") (pin "L01") (pinfunction "CIIN_L01") (pintype "input"))
      (node (ref "U3") (pin "16") (pinfunction "O4_16") (pintype "output"))
      (node (ref "U5") (pin "7") (pinfunction "I6_7") (pintype "input"))
    )
    (net (code "98") (name "/{slash}DSACK0") (class "Default")
      (node (ref "R1") (pin "1") (pinfunction "1_1") (pintype "passive"))
      (node (ref "U1") (pin "F01") (pinfunction "DSACK0_F01") (pintype "input"))
      (node (ref "U2") (pin "31") (pinfunction "DSACK0_31") (pintype "output"))
    )
    (net (code "99") (name "/{slash}DSACK1") (class "Default")
      (node (ref "R2") (pin "1") (pinfunction "1_1") (pintype "passive"))
      (node (ref "U1") (pin "G02") (pinfunction "DSACK1_G02") (pintype "input"))
      (node (ref "U2") (pin "32") (pinfunction "DSACK1_32") (pintype "output"))
      (node (ref "U4") (pin "12") (pinfunction "O8_12") (pintype "output"))
    )
    (net (code "100") (name "/{slash}DS_30") (class "Default")
      (node (ref "U1") (pin "K02") (pinfunction "DS_K02") (pintype "output"))
      (node (ref "U2") (pin "20") (pinfunction "DS_20") (pintype "input"))
    )
    (net (code "101") (name "/{slash}DTACK") (class "Default")
      (node (ref "CLASSIC_SOCKET") (pin "10") (pinfunction "DTACK_10") (pintype "input"))
      (node (ref "IC1") (pin "10") (pinfunction "DTACK_10") (pintype "input"))
      (node (ref "U$1") (pin "C6") (pinfunction "/DTACK_C6") (pintype "bidirectional"))
      (node (ref "U3") (pin "9") (pinfunction "I8_9") (pintype "input"))
    )
    (net (code "102") (name "/{slash}DTACK_SYS+EX") (class "Default")
      (node (ref "U3") (pin "15") (pinfunction "O5_15") (pintype "output"))
      (node (ref "U4") (pin "5") (pinfunction "I4_5") (pintype "input"))
    )
    (net (code "103") (name "/{slash}EXT.DTK") (class "Default")
      (node (ref "R16") (pin "1") (pinfunction "1_1") (pintype "passive"))
      (node (ref "U$1") (pin "B28") (pinfunction "/EXT.DTK_B28") (pintype "bidirectional"))
      (node (ref "U3") (pin "13") (pinfunction "O7_13") (pintype "output"))
    )
    (net (code "104") (name "/{slash}FPUCS") (class "Default")
      (node (ref "U2") (pin "29") (pinfunction "CS_29") (pintype "input"))
      (node (ref "U3") (pin "18") (pinfunction "O2_18") (pintype "output"))
      (node (ref "U6") (pin "6") (pinfunction "I5_6") (pintype "input"))
    )
    (net (code "105") (name "/{slash}HALT_30") (class "Default")
      (node (ref "R8") (pin "1") (pinfunction "1_1") (pintype "passive"))
      (node (ref "U1") (pin "H02") (pinfunction "HALT_H02") (pintype "input"))
    )
    (net (code "106") (name "/{slash}IPL0") (class "Default")
      (node (ref "CLASSIC_SOCKET") (pin "27") (pinfunction "IPL0_27") (pintype "input"))
      (node (ref "IC1") (pin "25") (pinfunction "IPL0_25") (pintype "input"))
      (node (ref "U$1") (pin "B18") (pinfunction "/IPL0_B18") (pintype "bidirectional"))
      (node (ref "U1") (pin "H13") (pinfunction "IPL0_H13") (pintype "input"))
    )
    (net (code "107") (name "/{slash}IPL1") (class "Default")
      (node (ref "CLASSIC_SOCKET") (pin "26") (pinfunction "IPL1_26") (pintype "input"))
      (node (ref "IC1") (pin "24") (pinfunction "IPL1_24") (pintype "input"))
      (node (ref "U$1") (pin "B19") (pinfunction "/IPL1_B19") (pintype "bidirectional"))
      (node (ref "U1") (pin "G13") (pinfunction "IPL1_G13") (pintype "input"))
    )
    (net (code "108") (name "/{slash}IPL2") (class "Default")
      (node (ref "CLASSIC_SOCKET") (pin "25") (pinfunction "IPL2_25") (pintype "input"))
      (node (ref "IC1") (pin "23") (pinfunction "IPL2_23") (pintype "input"))
      (node (ref "U$1") (pin "B20") (pinfunction "/IPL2_B20") (pintype "bidirectional"))
      (node (ref "U1") (pin "G12") (pinfunction "IPL2_G12") (pintype "input"))
      (node (ref "U5") (pin "6") (pinfunction "I5_6") (pintype "input"))
    )
    (net (code "109") (name "/{slash}LDS") (class "Default")
      (node (ref "CLASSIC_SOCKET") (pin "8") (pinfunction "LDS_8") (pintype "output"))
      (node (ref "IC1") (pin "8") (pinfunction "LDS_8") (pintype "output"))
      (node (ref "U$1") (pin "C8") (pinfunction "/LDS_C8") (pintype "bidirectional"))
      (node (ref "U5") (pin "19") (pinfunction "O1_19") (pintype "output"))
    )
    (net (code "110") (name "/{slash}MMUDIS") (class "Default")
      (node (ref "R12") (pin "1") (pinfunction "1_1") (pintype "passive"))
      (node (ref "U1") (pin "F13") (pinfunction "MMUDIS_F13") (pintype "input"))
    )
    (net (code "111") (name "/{slash}RESET_00") (class "Default")
      (node (ref "CLASSIC_SOCKET") (pin "20") (pinfunction "RESET_20") (pintype "bidirectional"))
      (node (ref "IC1") (pin "18") (pinfunction "RESET_18") (pintype "bidirectional"))
      (node (ref "U$1") (pin "C12") (pinfunction "/RESET_C12") (pintype "bidirectional"))
      (node (ref "U5") (pin "12") (pinfunction "O8_12") (pintype "output"))
    )
    (net (code "112") (name "/{slash}RESET_30") (class "Default")
      (node (ref "R3") (pin "1") (pinfunction "1_1") (pintype "passive"))
      (node (ref "U1") (pin "F12") (pinfunction "RESET_F12") (pintype "bidirectional"))
      (node (ref "U2") (pin "13") (pinfunction "RESET_13") (pintype "input"))
      (node (ref "U4") (pin "9") (pinfunction "I8_9") (pintype "input"))
      (node (ref "U5") (pin "13") (pinfunction "O7_13") (pintype "output"))
      (node (ref "U6") (pin "8") (pinfunction "I7_8") (pintype "input"))
    )
    (net (code "113") (name "/{slash}R{slash}W") (class "Default")
      (node (ref "CLASSIC_SOCKET") (pin "9") (pinfunction "R/W_9") (pintype "output"))
      (node (ref "IC1") (pin "9") (pinfunction "R/W_9") (pintype "output"))
      (node (ref "U$1") (pin "C7") (pinfunction "/R/W_C7") (pintype "bidirectional"))
      (node (ref "U1") (pin "L03") (pinfunction "R/~{W}_L03") (pintype "output"))
      (node (ref "U2") (pin "28") (pinfunction "R/~{W}_28") (pintype "input"))
      (node (ref "U4") (pin "8") (pinfunction "I7_8") (pintype "input"))
      (node (ref "U5") (pin "5") (pinfunction "I4_5") (pintype "input"))
    )
    (net (code "114") (name "/{slash}SCC.RW.DEC") (class "Default")
      (node (ref "U3") (pin "12") (pinfunction "O8_12") (pintype "output"))
      (node (ref "U6") (pin "9") (pinfunction "I8_9") (pintype "input"))
    )
    (net (code "115") (name "/{slash}STERM") (class "Default")
      (node (ref "R6") (pin "1") (pinfunction "1_1") (pintype "passive"))
      (node (ref "U1") (pin "G01") (pinfunction "STERM_G01") (pintype "input"))
    )
    (net (code "116") (name "/{slash}UDS") (class "Default")
      (node (ref "CLASSIC_SOCKET") (pin "7") (pinfunction "UDS_7") (pintype "output"))
      (node (ref "IC1") (pin "7") (pinfunction "UDS_7") (pintype "output"))
      (node (ref "U$1") (pin "C9") (pinfunction "/UDS_C9") (pintype "bidirectional"))
      (node (ref "U5") (pin "18") (pinfunction "O2_18") (pintype "output"))
    )
    (net (code "117") (name "/{slash}VMA") (class "Default")
      (node (ref "CLASSIC_SOCKET") (pin "21") (pinfunction "VMA_21") (pintype "output"))
      (node (ref "IC1") (pin "19") (pinfunction "VMA_19") (pintype "output"))
      (node (ref "U$1") (pin "C2") (pinfunction "/VMA_C2") (pintype "bidirectional"))
      (node (ref "U4") (pin "16") (pinfunction "O4_16") (pintype "output"))
    )
    (net (code "118") (name "/{slash}VPA") (class "Default")
      (node (ref "CLASSIC_SOCKET") (pin "23") (pinfunction "VPA_23") (pintype "input"))
      (node (ref "IC1") (pin "21") (pinfunction "VPA_21") (pintype "input"))
      (node (ref "U$1") (pin "C1") (pinfunction "/VPA_C1") (pintype "bidirectional"))
      (node (ref "U4") (pin "6") (pinfunction "I5_6") (pintype "input"))
    )
    (net (code "119") (name "GND") (class "Default")
      (node (ref "C1") (pin "-") (pinfunction "-_-") (pintype "passive"))
      (node (ref "C10") (pin "2") (pinfunction "2_2") (pintype "passive"))
      (node (ref "C11") (pin "2") (pinfunction "2_2") (pintype "passive"))
      (node (ref "C2") (pin "-") (pinfunction "-_-") (pintype "passive"))
      (node (ref "C3") (pin "-") (pinfunction "-_-") (pintype "passive"))
      (node (ref "C4") (pin "2") (pinfunction "2_2") (pintype "passive"))
      (node (ref "C5") (pin "2") (pinfunction "2_2") (pintype "passive"))
      (node (ref "C6") (pin "2") (pinfunction "2_2") (pintype "passive"))
      (node (ref "C7") (pin "2") (pinfunction "2_2") (pintype "passive"))
      (node (ref "C8") (pin "2") (pinfunction "2_2") (pintype "passive"))
      (node (ref "C9") (pin "2") (pinfunction "2_2") (pintype "passive"))
      (node (ref "QG1") (pin "7") (pinfunction "GND_7") (pintype "power_in"))
      (node (ref "U$1") (pin "A30") (pinfunction "GND_A30") (pintype "bidirectional"))
      (node (ref "U$1") (pin "B1") (pinfunction "GND_B1") (pintype "bidirectional"))
      (node (ref "U$1") (pin "B2") (pinfunction "GND_B2") (pintype "bidirectional"))
      (node (ref "U$1") (pin "B29") (pinfunction "GND_B29") (pintype "bidirectional"))
      (node (ref "U$1") (pin "B3") (pinfunction "GND_B3") (pintype "bidirectional"))
      (node (ref "U$1") (pin "B4") (pinfunction "GND_B4") (pintype "bidirectional"))
      (node (ref "U$1") (pin "B5") (pinfunction "GND_B5") (pintype "bidirectional"))
      (node (ref "U$1") (pin "B6") (pinfunction "GND_B6") (pintype "bidirectional"))
      (node (ref "U$1") (pin "B7") (pinfunction "GND_B7") (pintype "bidirectional"))
      (node (ref "U$1") (pin "B8") (pinfunction "GND_B8") (pintype "bidirectional"))
      (node (ref "U$1") (pin "B9") (pinfunction "GND_B9") (pintype "bidirectional"))
      (node (ref "U$1") (pin "C30") (pinfunction "GND_C30") (pintype "bidirectional"))
      (node (ref "U3") (pin "10") (pinfunction "GND_10") (pintype "power_in"))
      (node (ref "U4") (pin "10") (pinfunction "GND_10") (pintype "power_in"))
      (node (ref "U5") (pin "10") (pinfunction "GND_10") (pintype "power_in"))
      (node (ref "U5") (pin "11") (pinfunction "OE_11") (pintype "input"))
      (node (ref "U6") (pin "10") (pinfunction "GND_10") (pintype "power_in"))
      (node (ref "U6") (pin "11") (pinfunction "OE_11") (pintype "input"))
      (node (ref "U7") (pin "10") (pinfunction "GND_10") (pintype "power_in"))
    )
    (net (code "120") (name "Net-(U7-I3)") (class "Default")
      (node (ref "U7") (pin "16") (pinfunction "O4_16") (pintype "output"))
      (node (ref "U7") (pin "4") (pinfunction "I3_4") (pintype "input"))
    )
    (net (code "121") (name "Net-(U7-I4)") (class "Default")
      (node (ref "U7") (pin "15") (pinfunction "O5_15") (pintype "output"))
      (node (ref "U7") (pin "5") (pinfunction "I4_5") (pintype "input"))
    )
    (net (code "122") (name "Net-(U7-I5)") (class "Default")
      (node (ref "U7") (pin "14") (pinfunction "O6_14") (pintype "output"))
      (node (ref "U7") (pin "6") (pinfunction "I5_6") (pintype "input"))
    )
    (net (code "123") (name "VCC") (class "Default")
      (node (ref "C1") (pin "+") (pinfunction "+_+") (pintype "passive"))
      (node (ref "C10") (pin "1") (pinfunction "1_1") (pintype "passive"))
      (node (ref "C11") (pin "1") (pinfunction "1_1") (pintype "passive"))
      (node (ref "C2") (pin "+") (pinfunction "+_+") (pintype "passive"))
      (node (ref "C3") (pin "+") (pinfunction "+_+") (pintype "passive"))
      (node (ref "C4") (pin "1") (pinfunction "1_1") (pintype "passive"))
      (node (ref "C5") (pin "1") (pinfunction "1_1") (pintype "passive"))
      (node (ref "C6") (pin "1") (pinfunction "1_1") (pintype "passive"))
      (node (ref "C7") (pin "1") (pinfunction "1_1") (pintype "passive"))
      (node (ref "C8") (pin "1") (pinfunction "1_1") (pintype "passive"))
      (node (ref "C9") (pin "1") (pinfunction "1_1") (pintype "passive"))
      (node (ref "QG1") (pin "14") (pinfunction "VCC_14") (pintype "power_in"))
      (node (ref "R1") (pin "2") (pinfunction "2_2") (pintype "passive"))
      (node (ref "R10") (pin "2") (pinfunction "2_2") (pintype "passive"))
      (node (ref "R11") (pin "2") (pinfunction "2_2") (pintype "passive"))
      (node (ref "R12") (pin "2") (pinfunction "2_2") (pintype "passive"))
      (node (ref "R13") (pin "2") (pinfunction "2_2") (pintype "passive"))
      (node (ref "R14") (pin "2") (pinfunction "2_2") (pintype "passive"))
      (node (ref "R15") (pin "2") (pinfunction "2_2") (pintype "passive"))
      (node (ref "R16") (pin "2") (pinfunction "2_2") (pintype "passive"))
      (node (ref "R17") (pin "2") (pinfunction "2_2") (pintype "passive"))
      (node (ref "R18") (pin "2") (pinfunction "2_2") (pintype "passive"))
      (node (ref "R2") (pin "2") (pinfunction "2_2") (pintype "passive"))
      (node (ref "R3") (pin "2") (pinfunction "2_2") (pintype "passive"))
      (node (ref "R4") (pin "2") (pinfunction "2_2") (pintype "passive"))
      (node (ref "R5") (pin "2") (pinfunction "2_2") (pintype "passive"))
      (node (ref "R6") (pin "2") (pinfunction "2_2") (pintype "passive"))
      (node (ref "R7") (pin "2") (pinfunction "2_2") (pintype "passive"))
      (node (ref "R8") (pin "2") (pinfunction "2_2") (pintype "passive"))
      (node (ref "R9") (pin "2") (pinfunction "2_2") (pintype "passive"))
      (node (ref "U$1") (pin "B13") (pinfunction "VCC_B13") (pintype "bidirectional"))
      (node (ref "U$1") (pin "B14") (pinfunction "VCC_B14") (pintype "bidirectional"))
      (node (ref "U$1") (pin "B15") (pinfunction "VCC_B15") (pintype "bidirectional"))
      (node (ref "U$1") (pin "B16") (pinfunction "VCC_B16") (pintype "bidirectional"))
      (node (ref "U$1") (pin "B17") (pinfunction "VCC_B17") (pintype "bidirectional"))
      (node (ref "U$1") (pin "C13") (pinfunction "VCC_C13") (pintype "bidirectional"))
      (node (ref "U3") (pin "20") (pinfunction "VCC_20") (pintype "power_in"))
      (node (ref "U4") (pin "20") (pinfunction "VCC_20") (pintype "power_in"))
      (node (ref "U5") (pin "20") (pinfunction "VCC_20") (pintype "power_in"))
      (node (ref "U6") (pin "20") (pinfunction "VCC_20") (pintype "power_in"))
      (node (ref "U7") (pin "20") (pinfunction "VCC_20") (pintype "power_in"))
    )
    (net (code "124") (name "unconnected-(CLASSIC_SOCKETA-BERR-Pad24)") (class "Default")
      (node (ref "CLASSIC_SOCKET") (pin "24") (pinfunction "BERR_24") (pintype "input"))
    )
    (net (code "125") (name "unconnected-(CLASSIC_SOCKETA-BG-Pad11)") (class "Default")
      (node (ref "CLASSIC_SOCKET") (pin "11") (pinfunction "BG_11") (pintype "output"))
    )
    (net (code "126") (name "unconnected-(CLASSIC_SOCKETA-BGACK-Pad12)") (class "Default")
      (node (ref "CLASSIC_SOCKET") (pin "12") (pinfunction "BGACK_12") (pintype "input"))
    )
    (net (code "127") (name "unconnected-(CLASSIC_SOCKETA-HALT-Pad19)") (class "Default")
      (node (ref "CLASSIC_SOCKET") (pin "19") (pinfunction "HALT_19") (pintype "bidirectional"))
    )
    (net (code "128") (name "unconnected-(IC1A-BERR-Pad22)") (class "Default")
      (node (ref "IC1") (pin "22") (pinfunction "BERR_22") (pintype "input"))
    )
    (net (code "129") (name "unconnected-(IC1A-BG-Pad11)") (class "Default")
      (node (ref "IC1") (pin "11") (pinfunction "BG_11") (pintype "output"))
    )
    (net (code "130") (name "unconnected-(IC1A-BGACK-Pad12)") (class "Default")
      (node (ref "IC1") (pin "12") (pinfunction "BGACK_12") (pintype "input"))
    )
    (net (code "131") (name "unconnected-(IC1A-HALT-Pad17)") (class "Default")
      (node (ref "IC1") (pin "17") (pinfunction "HALT_17") (pintype "bidirectional"))
    )
    (net (code "132") (name "unconnected-(U$1-+12V-PadA31)") (class "Default")
      (node (ref "U$1") (pin "A31") (pinfunction "+12V_A31") (pintype "bidirectional"))
    )
    (net (code "133") (name "unconnected-(U$1-+12V-PadA32)") (class "Default")
      (node (ref "U$1") (pin "A32") (pinfunction "+12V_A32") (pintype "bidirectional"))
    )
    (net (code "134") (name "unconnected-(U$1-+12V-PadB30)") (class "Default")
      (node (ref "U$1") (pin "B30") (pinfunction "+12V_B30") (pintype "bidirectional"))
    )
    (net (code "135") (name "unconnected-(U$1-+12V-PadB31)") (class "Default")
      (node (ref "U$1") (pin "B31") (pinfunction "+12V_B31") (pintype "bidirectional"))
    )
    (net (code "136") (name "unconnected-(U$1--5V-PadB32)") (class "Default")
      (node (ref "U$1") (pin "B32") (pinfunction "-5V_B32") (pintype "bidirectional"))
    )
    (net (code "137") (name "unconnected-(U$1--12V-PadC32)") (class "Default")
      (node (ref "U$1") (pin "C32") (pinfunction "-12V_C32") (pintype "bidirectional"))
    )
    (net (code "138") (name "unconnected-(U$1-RESERVED-PadB10)") (class "Default")
      (node (ref "U$1") (pin "B10") (pinfunction "RESERVED_B10") (pintype "bidirectional"))
    )
    (net (code "139") (name "unconnected-(U$1-RESERVED-PadB11)") (class "Default")
      (node (ref "U$1") (pin "B11") (pinfunction "RESERVED_B11") (pintype "bidirectional"))
    )
    (net (code "140") (name "unconnected-(U$1-RESERVED-PadB23)") (class "Default")
      (node (ref "U$1") (pin "B23") (pinfunction "RESERVED_B23") (pintype "bidirectional"))
    )
    (net (code "141") (name "unconnected-(U$1-RESERVED-PadB24)") (class "Default")
      (node (ref "U$1") (pin "B24") (pinfunction "RESERVED_B24") (pintype "bidirectional"))
    )
    (net (code "142") (name "unconnected-(U$1-RESERVED-PadB25)") (class "Default")
      (node (ref "U$1") (pin "B25") (pinfunction "RESERVED_B25") (pintype "bidirectional"))
    )
    (net (code "143") (name "unconnected-(U$1-RESERVED-PadB26)") (class "Default")
      (node (ref "U$1") (pin "B26") (pinfunction "RESERVED_B26") (pintype "bidirectional"))
    )
    (net (code "144") (name "unconnected-(U$1-RESERVED-PadB27)") (class "Default")
      (node (ref "U$1") (pin "B27") (pinfunction "RESERVED_B27") (pintype "bidirectional"))
    )
    (net (code "145") (name "unconnected-(U$1-SPARE-PadB22)") (class "Default")
      (node (ref "U$1") (pin "B22") (pinfunction "SPARE_B22") (pintype "bidirectional"))
    )
    (net (code "146") (name "unconnected-(U$1-SPARE-PadC31)") (class "Default")
      (node (ref "U$1") (pin "C31") (pinfunction "SPARE_C31") (pintype "bidirectional"))
    )
    (net (code "147") (name "unconnected-(U$1-{slash}BERR-PadB21)") (class "Default")
      (node (ref "U$1") (pin "B21") (pinfunction "/BERR_B21") (pintype "bidirectional"))
    )
    (net (code "148") (name "unconnected-(U$1-{slash}BG-PadC5)") (class "Default")
      (node (ref "U$1") (pin "C5") (pinfunction "/BG_C5") (pintype "bidirectional"))
    )
    (net (code "149") (name "unconnected-(U$1-{slash}BGACK-PadC4)") (class "Default")
      (node (ref "U$1") (pin "C4") (pinfunction "/BGACK_C4") (pintype "bidirectional"))
    )
    (net (code "150") (name "unconnected-(U$1-{slash}HALT-PadB12)") (class "Default")
      (node (ref "U$1") (pin "B12") (pinfunction "/HALT_B12") (pintype "bidirectional"))
    )
    (net (code "151") (name "unconnected-(U$1-{slash}PMCYC-PadC11)") (class "Default")
      (node (ref "U$1") (pin "C11") (pinfunction "/PMCYC_C11") (pintype "bidirectional"))
    )
    (net (code "152") (name "unconnected-(U1A-A24-PadA06)") (class "Default")
      (node (ref "U1") (pin "A06") (pinfunction "A24_A06") (pintype "output"))
    )
    (net (code "153") (name "unconnected-(U1A-A25-PadB06)") (class "Default")
      (node (ref "U1") (pin "B06") (pinfunction "A25_B06") (pintype "output"))
    )
    (net (code "154") (name "unconnected-(U1A-A26-PadA05)") (class "Default")
      (node (ref "U1") (pin "A05") (pinfunction "A26_A05") (pintype "output"))
    )
    (net (code "155") (name "unconnected-(U1A-A27-PadB05)") (class "Default")
      (node (ref "U1") (pin "B05") (pinfunction "A27_B05") (pintype "output"))
    )
    (net (code "156") (name "unconnected-(U1A-A28-PadA04)") (class "Default")
      (node (ref "U1") (pin "A04") (pinfunction "A28_A04") (pintype "output"))
    )
    (net (code "157") (name "unconnected-(U1A-A29-PadB04)") (class "Default")
      (node (ref "U1") (pin "B04") (pinfunction "A29_B04") (pintype "output"))
    )
    (net (code "158") (name "unconnected-(U1A-A30-PadA03)") (class "Default")
      (node (ref "U1") (pin "A03") (pinfunction "A30_A03") (pintype "output"))
    )
    (net (code "159") (name "unconnected-(U1A-A31-PadB03)") (class "Default")
      (node (ref "U1") (pin "B03") (pinfunction "A31_B03") (pintype "output"))
    )
    (net (code "160") (name "unconnected-(U1A-BG-PadB02)") (class "Default")
      (node (ref "U1") (pin "B02") (pinfunction "BG_B02") (pintype "output"))
    )
    (net (code "161") (name "unconnected-(U1A-CBREQ-PadK01)") (class "Default")
      (node (ref "U1") (pin "K01") (pinfunction "CBREQ_K01") (pintype "output"))
    )
    (net (code "162") (name "unconnected-(U1A-CIOUT-PadC02)") (class "Default")
      (node (ref "U1") (pin "C02") (pinfunction "CIOUT_C02") (pintype "output"))
    )
    (net (code "163") (name "unconnected-(U1A-DBEN-PadM01)") (class "Default")
      (node (ref "U1") (pin "M01") (pinfunction "DBEN_M01") (pintype "output"))
    )
    (net (code "164") (name "unconnected-(U1A-IPEND-PadE13)") (class "Default")
      (node (ref "U1") (pin "E13") (pinfunction "IPEND_E13") (pintype "output"))
    )
    (net (code "165") (name "unconnected-(U1A-OCS-PadD03)") (class "Default")
      (node (ref "U1") (pin "D03") (pinfunction "OCS_D03") (pintype "output"))
    )
    (net (code "166") (name "unconnected-(U1A-REFILL-PadJ13)") (class "Default")
      (node (ref "U1") (pin "J13") (pinfunction "REFILL_J13") (pintype "output"))
    )
    (net (code "167") (name "unconnected-(U1A-RMC-PadB01)") (class "Default")
      (node (ref "U1") (pin "B01") (pinfunction "RMC_B01") (pintype "output"))
    )
    (net (code "168") (name "unconnected-(U1A-STATUS-PadJ12)") (class "Default")
      (node (ref "U1") (pin "J12") (pinfunction "STATUS_J12") (pintype "output"))
    )
    (net (code "169") (name "unconnected-(U3-O6-Pad14)") (class "Default")
      (node (ref "U3") (pin "14") (pinfunction "O6_14") (pintype "output"))
    )
    (net (code "170") (name "unconnected-(U4-O3-Pad17)") (class "Default")
      (node (ref "U4") (pin "17") (pinfunction "O3_17") (pintype "output"))
    )
    (net (code "171") (name "unconnected-(U4-O5-Pad15)") (class "Default")
      (node (ref "U4") (pin "15") (pinfunction "O5_15") (pintype "output"))
    )
    (net (code "172") (name "unconnected-(U4-O6-Pad14)") (class "Default")
      (node (ref "U4") (pin "14") (pinfunction "O6_14") (pintype "output"))
    )
    (net (code "173") (name "unconnected-(U5-O5-Pad15)") (class "Default")
      (node (ref "U5") (pin "15") (pinfunction "O5_15") (pintype "output"))
    )
    (net (code "174") (name "unconnected-(U5-O6-Pad14)") (class "Default")
      (node (ref "U5") (pin "14") (pinfunction "O6_14") (pintype "output"))
    )
    (net (code "175") (name "unconnected-(U6-O3-Pad17)") (class "Default")
      (node (ref "U6") (pin "17") (pinfunction "O3_17") (pintype "output"))
    )
    (net (code "176") (name "unconnected-(U6-O4-Pad16)") (class "Default")
      (node (ref "U6") (pin "16") (pinfunction "O4_16") (pintype "output"))
    )
    (net (code "177") (name "unconnected-(U6-O5-Pad15)") (class "Default")
      (node (ref "U6") (pin "15") (pinfunction "O5_15") (pintype "output"))
    )
    (net (code "178") (name "unconnected-(U7-CLK-Pad1)") (class "Default")
      (node (ref "U7") (pin "1") (pinfunction "CLK_1") (pintype "input"))
    )
    (net (code "179") (name "unconnected-(U7-I1-Pad2)") (class "Default")
      (node (ref "U7") (pin "2") (pinfunction "I1_2") (pintype "input"))
    )
    (net (code "180") (name "unconnected-(U7-I6-Pad7)") (class "Default")
      (node (ref "U7") (pin "7") (pinfunction "I6_7") (pintype "input"))
    )
    (net (code "181") (name "unconnected-(U7-I7-Pad8)") (class "Default")
      (node (ref "U7") (pin "8") (pinfunction "I7_8") (pintype "input"))
    )
    (net (code "182") (name "unconnected-(U7-I8-Pad9)") (class "Default")
      (node (ref "U7") (pin "9") (pinfunction "I8_9") (pintype "input"))
    )
    (net (code "183") (name "unconnected-(U7-O1-Pad19)") (class "Default")
      (node (ref "U7") (pin "19") (pinfunction "O1_19") (pintype "output"))
    )
    (net (code "184") (name "unconnected-(U7-O2-Pad18)") (class "Default")
      (node (ref "U7") (pin "18") (pinfunction "O2_18") (pintype "output"))
    )
    (net (code "185") (name "unconnected-(U7-O3-Pad17)") (class "Default")
      (node (ref "U7") (pin "17") (pinfunction "O3_17") (pintype "output"))
    )
    (net (code "186") (name "unconnected-(U7-O8-Pad12)") (class "Default")
      (node (ref "U7") (pin "12") (pinfunction "O8_12") (pintype "output"))
    )
    (net (code "187") (name "unconnected-(U7-OE-Pad11)") (class "Default")
      (node (ref "U7") (pin "11") (pinfunction "OE_11") (pintype "input"))
    )
  )
)
